# 12_IO_PORT.net
KiCad netlist of a schematic drawn in Altium Designer
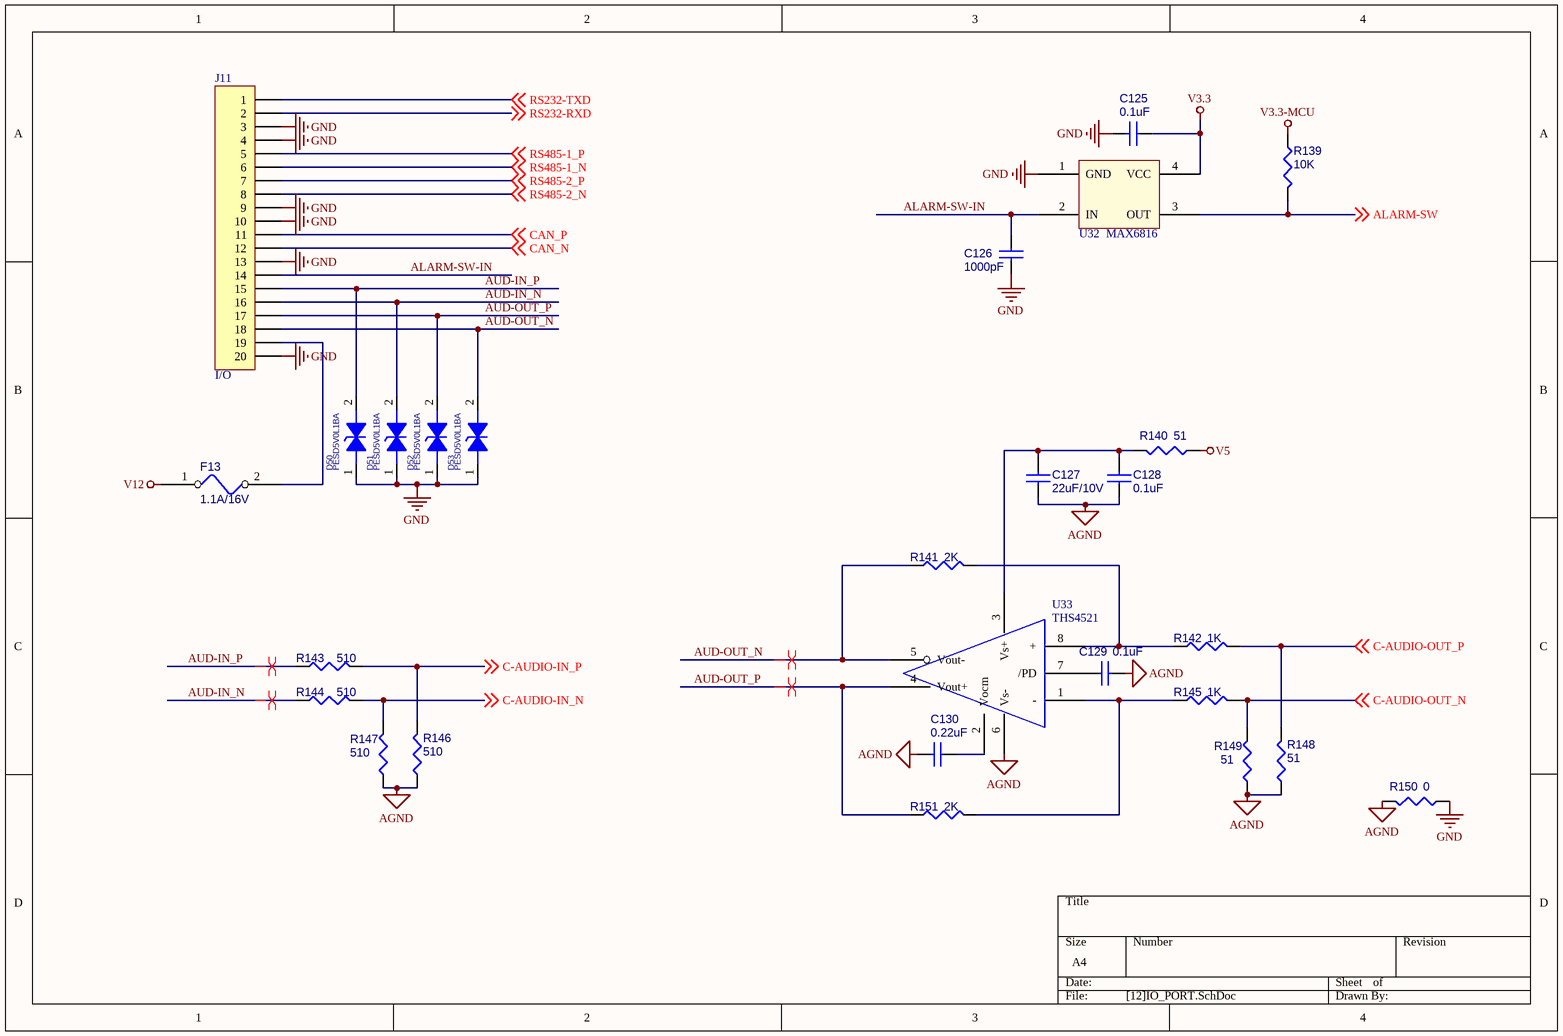
[diagram p0: [12]IO_PORT.SchDoc]

(export (version "E")
  (design (tool "Eeschema 10.0.6"))
  (components
    (comp (ref "C125") (value "0.1uF") (libsource (lib "*") (part "CAP")))
    (comp (ref "C126") (value "1000pF") (libsource (lib "*") (part "CAP")))
    (comp (ref "C127") (value "22uF/10V") (footprint "1210") (libsource (lib "*") (part "P_CAP NP")))
    (comp (ref "C128") (value "0.1uF") (footprint "0603") (libsource (lib "*") (part "P_CAP NP")))
    (comp (ref "C129") (value "0.1uF") (footprint "0603") (libsource (lib "*") (part "P_CAP NP")))
    (comp (ref "C130") (value "0.22uF") (footprint "0603") (libsource (lib "*") (part "P_CAP NP")))
    (comp (ref "D50") (value "PESD5V0L1BA") (libsource (lib "*") (part "PESD")))
    (comp (ref "D51") (value "PESD5V0L1BA") (libsource (lib "*") (part "PESD")))
    (comp (ref "D52") (value "PESD5V0L1BA") (libsource (lib "*") (part "PESD")))
    (comp (ref "D53") (value "PESD5V0L1BA") (libsource (lib "*") (part "PESD")))
    (comp (ref "F13") (value "1.1A/16V") (libsource (lib "*") (part "2A_32VDC_0467-002")))
    (comp (ref "J11")
      (value "I/O")
      (footprint "COMM-3MM-2X10")
      (description "Header, 20-Pin")
      (fields (field (name "PUBLISHER") "Altium Limited"))
      (libsource (lib "Miscellaneous Connectors") (part "Header 20"))
    )
    (comp (ref "R139") (value "10K") (libsource (lib "*") (part "R")))
    (comp (ref "R140") (value "51") (footprint "0603") (libsource (lib "*") (part "P_R")))
    (comp (ref "R141") (value "2K") (footprint "0603") (libsource (lib "*") (part "P_R")))
    (comp (ref "R142") (value "1K") (footprint "0603") (libsource (lib "*") (part "P_R")))
    (comp (ref "R143") (value "510") (footprint "0603") (libsource (lib "*") (part "P_R")))
    (comp (ref "R144") (value "510") (footprint "0603") (libsource (lib "*") (part "P_R")))
    (comp (ref "R145") (value "1K") (footprint "0603") (libsource (lib "*") (part "P_R")))
    (comp (ref "R146") (value "510") (footprint "0603") (libsource (lib "*") (part "P_R")))
    (comp (ref "R147") (value "510") (footprint "0603") (libsource (lib "*") (part "P_R")))
    (comp (ref "R148") (value "51") (footprint "0603") (libsource (lib "*") (part "P_R")))
    (comp (ref "R149") (value "51") (footprint "0603") (libsource (lib "*") (part "P_R")))
    (comp (ref "R150") (value "0") (footprint "0603") (libsource (lib "*") (part "P_R")))
    (comp (ref "R151") (value "2K") (footprint "0603") (libsource (lib "*") (part "P_R")))
    (comp (ref "U32") (value "MAX6816") (footprint "SOT143") (libsource (lib "Schlib") (part "MAX6816")))
    (comp (ref "U33") (value "THS4521") (footprint "SO8") (libsource (lib "Schlib") (part "THS4521")))
  )
  (nets
    (net (code "1") (name "/ALARM-SW-IN") (class "Default")
      (node (ref "C126") (pin "1") (pinfunction "1_1") (pintype "passive"))
      (node (ref "J11") (pin "14") (pinfunction "14_14") (pintype "passive"))
      (node (ref "U32") (pin "2") (pinfunction "IN_2") (pintype "passive"))
    )
    (net (code "2") (name "/AUD-IN_N") (class "Default")
      (node (ref "D51") (pin "2") (pinfunction "2_2") (pintype "passive"))
      (node (ref "J11") (pin "16") (pinfunction "16_16") (pintype "passive"))
      (node (ref "R144") (pin "2") (pinfunction "2_2") (pintype "passive"))
    )
    (net (code "3") (name "/AUD-IN_P") (class "Default")
      (node (ref "D50") (pin "2") (pinfunction "2_2") (pintype "passive"))
      (node (ref "J11") (pin "15") (pinfunction "15_15") (pintype "passive"))
      (node (ref "R143") (pin "2") (pinfunction "2_2") (pintype "passive"))
    )
    (net (code "4") (name "/AUD-OUT_N") (class "Default")
      (node (ref "D53") (pin "2") (pinfunction "2_2") (pintype "passive"))
      (node (ref "J11") (pin "18") (pinfunction "18_18") (pintype "passive"))
      (node (ref "R141") (pin "2") (pinfunction "2_2") (pintype "passive"))
      (node (ref "U33") (pin "5") (pinfunction "Vout-_5") (pintype "passive"))
    )
    (net (code "5") (name "/AUD-OUT_P") (class "Default")
      (node (ref "D52") (pin "2") (pinfunction "2_2") (pintype "passive"))
      (node (ref "J11") (pin "17") (pinfunction "17_17") (pintype "passive"))
      (node (ref "R151") (pin "2") (pinfunction "2_2") (pintype "passive"))
      (node (ref "U33") (pin "4") (pinfunction "Vout+_4") (pintype "passive"))
    )
    (net (code "6") (name "AGND") (class "Default")
      (node (ref "C127") (pin "1") (pinfunction "1_1") (pintype "passive"))
      (node (ref "C128") (pin "1") (pinfunction "1_1") (pintype "passive"))
      (node (ref "C129") (pin "2") (pinfunction "2_2") (pintype "passive"))
      (node (ref "C130") (pin "2") (pinfunction "2_2") (pintype "passive"))
      (node (ref "R146") (pin "2") (pinfunction "2_2") (pintype "passive"))
      (node (ref "R147") (pin "2") (pinfunction "2_2") (pintype "passive"))
      (node (ref "R148") (pin "2") (pinfunction "2_2") (pintype "passive"))
      (node (ref "R149") (pin "2") (pinfunction "2_2") (pintype "passive"))
      (node (ref "R150") (pin "1") (pinfunction "1_1") (pintype "passive"))
      (node (ref "U33") (pin "6") (pinfunction "Vs-_6") (pintype "passive"))
    )
    (net (code "7") (name "ALARM-SW") (class "Default")
      (node (ref "R139") (pin "2") (pinfunction "2_2") (pintype "passive"))
      (node (ref "U32") (pin "3") (pinfunction "OUT_3") (pintype "passive"))
    )
    (net (code "8") (name "C-AUDIO-IN_N") (class "Default")
      (node (ref "R144") (pin "1") (pinfunction "1_1") (pintype "passive"))
      (node (ref "R147") (pin "1") (pinfunction "1_1") (pintype "passive"))
    )
    (net (code "9") (name "C-AUDIO-IN_P") (class "Default")
      (node (ref "R143") (pin "1") (pinfunction "1_1") (pintype "passive"))
      (node (ref "R146") (pin "1") (pinfunction "1_1") (pintype "passive"))
    )
    (net (code "10") (name "C-AUDIO-OUT_N") (class "Default")
      (node (ref "R145") (pin "1") (pinfunction "1_1") (pintype "passive"))
      (node (ref "R149") (pin "1") (pinfunction "1_1") (pintype "passive"))
    )
    (net (code "11") (name "C-AUDIO-OUT_P") (class "Default")
      (node (ref "R142") (pin "1") (pinfunction "1_1") (pintype "passive"))
      (node (ref "R148") (pin "1") (pinfunction "1_1") (pintype "passive"))
    )
    (net (code "12") (name "CAN_N") (class "Default")
      (node (ref "J11") (pin "12") (pinfunction "12_12") (pintype "passive"))
    )
    (net (code "13") (name "CAN_P") (class "Default")
      (node (ref "J11") (pin "11") (pinfunction "11_11") (pintype "passive"))
    )
    (net (code "14") (name "GND") (class "Default")
      (node (ref "C125") (pin "2") (pinfunction "2_2") (pintype "passive"))
      (node (ref "C126") (pin "2") (pinfunction "2_2") (pintype "passive"))
      (node (ref "D50") (pin "1") (pinfunction "1_1") (pintype "passive"))
      (node (ref "D51") (pin "1") (pinfunction "1_1") (pintype "passive"))
      (node (ref "D52") (pin "1") (pinfunction "1_1") (pintype "passive"))
      (node (ref "D53") (pin "1") (pinfunction "1_1") (pintype "passive"))
      (node (ref "J11") (pin "10") (pinfunction "10_10") (pintype "passive"))
      (node (ref "J11") (pin "13") (pinfunction "13_13") (pintype "passive"))
      (node (ref "J11") (pin "20") (pinfunction "20_20") (pintype "passive"))
      (node (ref "J11") (pin "3") (pinfunction "3_3") (pintype "passive"))
      (node (ref "J11") (pin "4") (pinfunction "4_4") (pintype "passive"))
      (node (ref "J11") (pin "9") (pinfunction "9_9") (pintype "passive"))
      (node (ref "R150") (pin "2") (pinfunction "2_2") (pintype "passive"))
      (node (ref "U32") (pin "1") (pinfunction "GND_1") (pintype "passive"))
    )
    (net (code "15") (name "Net-(F13-Pad2)") (class "Default")
      (node (ref "F13") (pin "2") (pinfunction "2_2") (pintype "passive"))
      (node (ref "J11") (pin "19") (pinfunction "19_19") (pintype "passive"))
    )
    (net (code "16") (name "Net-(U33-+)") (class "Default")
      (node (ref "R141") (pin "1") (pinfunction "1_1") (pintype "passive"))
      (node (ref "R142") (pin "2") (pinfunction "2_2") (pintype "passive"))
      (node (ref "U33") (pin "8") (pinfunction "+_8") (pintype "passive"))
    )
    (net (code "17") (name "Net-(U33--)") (class "Default")
      (node (ref "R145") (pin "2") (pinfunction "2_2") (pintype "passive"))
      (node (ref "R151") (pin "1") (pinfunction "1_1") (pintype "passive"))
      (node (ref "U33") (pin "1") (pinfunction "-_1") (pintype "passive"))
    )
    (net (code "18") (name "Net-(U33-Vocm)") (class "Default")
      (node (ref "C130") (pin "1") (pinfunction "1_1") (pintype "passive"))
      (node (ref "U33") (pin "2") (pinfunction "Vocm_2") (pintype "passive"))
    )
    (net (code "19") (name "Net-(U33-Vs+)") (class "Default")
      (node (ref "C127") (pin "2") (pinfunction "2_2") (pintype "passive"))
      (node (ref "C128") (pin "2") (pinfunction "2_2") (pintype "passive"))
      (node (ref "R140") (pin "1") (pinfunction "1_1") (pintype "passive"))
      (node (ref "U33") (pin "3") (pinfunction "Vs+_3") (pintype "passive"))
    )
    (net (code "20") (name "Net-(U33-{slash}PD)") (class "Default")
      (node (ref "C129") (pin "1") (pinfunction "1_1") (pintype "passive"))
      (node (ref "U33") (pin "7") (pinfunction "/PD_7") (pintype "passive"))
    )
    (net (code "21") (name "RS232-RXD") (class "Default")
      (node (ref "J11") (pin "2") (pinfunction "2_2") (pintype "passive"))
    )
    (net (code "22") (name "RS232-TXD") (class "Default")
      (node (ref "J11") (pin "1") (pinfunction "1_1") (pintype "passive"))
    )
    (net (code "23") (name "RS485-1_N") (class "Default")
      (node (ref "J11") (pin "6") (pinfunction "6_6") (pintype "passive"))
    )
    (net (code "24") (name "RS485-1_P") (class "Default")
      (node (ref "J11") (pin "5") (pinfunction "5_5") (pintype "passive"))
    )
    (net (code "25") (name "RS485-2_N") (class "Default")
      (node (ref "J11") (pin "8") (pinfunction "8_8") (pintype "passive"))
    )
    (net (code "26") (name "RS485-2_P") (class "Default")
      (node (ref "J11") (pin "7") (pinfunction "7_7") (pintype "passive"))
    )
    (net (code "27") (name "V3.3") (class "Default")
      (node (ref "C125") (pin "1") (pinfunction "1_1") (pintype "passive"))
      (node (ref "U32") (pin "4") (pinfunction "VCC_4") (pintype "passive"))
    )
    (net (code "28") (name "V3.3-MCU") (class "Default")
      (node (ref "R139") (pin "1") (pinfunction "1_1") (pintype "passive"))
    )
    (net (code "29") (name "V5") (class "Default")
      (node (ref "R140") (pin "2") (pinfunction "2_2") (pintype "passive"))
    )
    (net (code "30") (name "V12") (class "Default")
      (node (ref "F13") (pin "1") (pinfunction "1_1") (pintype "passive"))
    )
  )
)
